# SCH_3_3v_regulator.net
KiCad netlist of a schematic drawn in Altium Designer
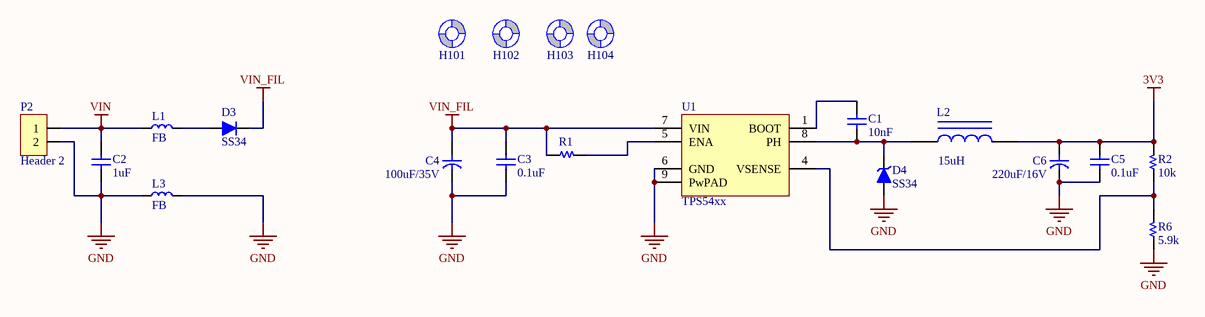
[diagram p0: SCH_3.3v_regulator.SchDoc]

(export (version "E")
  (design (tool "Eeschema 10.0.6"))
  (components
    (comp (ref "C1")
      (value "10nF")
      (footprint "C 0805")
      (description "Capacitor non-pol")
      (libsource (lib "chipfc_libs") (part "Capacitor NP"))
    )
    (comp (ref "C2")
      (value "1uF")
      (footprint "C 0805")
      (description "Capacitor non-pol")
      (libsource (lib "chipfc_libs") (part "Capacitor NP"))
    )
    (comp (ref "C3")
      (value "0.1uF")
      (footprint "C 0805")
      (description "Capacitor non-pol")
      (libsource (lib "chipfc_libs") (part "Capacitor NP"))
    )
    (comp (ref "C4")
      (value "100uF/35V")
      (footprint "C SMD ALU (D8)")
      (description "Capacitor pol")
      (libsource (lib "chipfc_libs") (part "Capacitor"))
    )
    (comp (ref "C5")
      (value "0.1uF")
      (footprint "C 0805")
      (description "Capacitor non-pol")
      (libsource (lib "chipfc_libs") (part "Capacitor NP"))
    )
    (comp (ref "C6")
      (value "220uF/16V")
      (footprint "C SMD ALU (D8)")
      (description "Capacitor pol")
      (libsource (lib "chipfc_libs") (part "Capacitor"))
    )
    (comp (ref "D3")
      (value "SS34")
      (footprint "Diode PowerDI123")
      (description "Default Diode")
      (libsource (lib "chipfc_libs") (part "Diode"))
    )
    (comp (ref "D4")
      (value "SS34")
      (footprint "DO-214AC (SMA)")
      (description "Zener Diode")
      (libsource (lib "chipfc_libs") (part "Diode Zener"))
    )
    (comp (ref "H101")
      (value "Screw Hole")
      (footprint "SCREW/3.2/7.0/M")
      (libsource (lib "chipfc_libs") (part "Screw Hole"))
    )
    (comp (ref "H102")
      (value "Screw Hole")
      (footprint "SCREW/3.2/7.0/M")
      (libsource (lib "chipfc_libs") (part "Screw Hole"))
    )
    (comp (ref "H103")
      (value "Screw Hole")
      (footprint "SCREW/3.2/7.0/M")
      (libsource (lib "chipfc_libs") (part "Screw Hole"))
    )
    (comp (ref "H104")
      (value "Screw Hole")
      (footprint "SCREW/3.2/7.0/M")
      (libsource (lib "chipfc_libs") (part "Screw Hole"))
    )
    (comp (ref "L1")
      (value "FB")
      (footprint "L 0805 (2012)")
      (description "Inductor")
      (libsource (lib "chipfc_libs") (part "Inductor"))
    )
    (comp (ref "L2")
      (value "15uH")
      (footprint "AXIAL-0.9")
      (description "Magnetic-Core Inductor")
      (fields (field (name "PUBLISHER") "Altium Limited"))
      (libsource (lib "Miscellaneous-Devices") (part "Inductor Iron"))
    )
    (comp (ref "L3")
      (value "FB")
      (footprint "L 0805 (2012)")
      (description "Inductor")
      (libsource (lib "chipfc_libs") (part "Inductor"))
    )
    (comp (ref "P2")
      (value "Header 2")
      (footprint "HDR/Header/2/BOX")
      (description "Header, 2-Pin")
      (libsource (lib "connectors") (part "Header 2"))
    )
    (comp (ref "R1")
      (value "R")
      (footprint "R 0805")
      (description "Resistor")
      (libsource (lib "chipfc_libs") (part "Resistor"))
    )
    (comp (ref "R2")
      (value "10k")
      (footprint "R 0805")
      (description "Resistor")
      (libsource (lib "chipfc_libs") (part "Resistor"))
    )
    (comp (ref "R6")
      (value "5.9k")
      (footprint "R 0805")
      (description "Resistor")
      (libsource (lib "chipfc_libs") (part "Resistor"))
    )
    (comp (ref "U1")
      (value "TPS54xx")
      (footprint "SOIC-8 EP")
      (description "3/5A, Wide input range, Step-down SWIFT DC-DC Converter")
      (libsource (lib "chipfc_libs") (part "TPS54xx"))
    )
  )
  (nets
    (net (code "1") (name "3V3") (class "Default")
      (node (ref "C5") (pin "1") (pinfunction "1_1") (pintype "passive"))
      (node (ref "C6") (pin "1") (pinfunction "1_1") (pintype "passive"))
      (node (ref "L2") (pin "2") (pinfunction "2_2") (pintype "passive"))
      (node (ref "R2") (pin "2") (pinfunction "2_2") (pintype "passive"))
    )
    (net (code "2") (name "GND") (class "Default")
      (node (ref "C2") (pin "2") (pinfunction "2_2") (pintype "passive"))
      (node (ref "C3") (pin "2") (pinfunction "2_2") (pintype "passive"))
      (node (ref "C4") (pin "2") (pinfunction "2_2") (pintype "passive"))
      (node (ref "C5") (pin "2") (pinfunction "2_2") (pintype "passive"))
      (node (ref "C6") (pin "2") (pinfunction "2_2") (pintype "passive"))
      (node (ref "D4") (pin "1") (pinfunction "A_1") (pintype "passive"))
      (node (ref "L3") (pin "1") (pinfunction "1_1") (pintype "passive"))
      (node (ref "L3") (pin "2") (pinfunction "2_2") (pintype "passive"))
      (node (ref "P2") (pin "2") (pinfunction "2_2") (pintype "passive"))
      (node (ref "R6") (pin "1") (pinfunction "1_1") (pintype "passive"))
      (node (ref "U1") (pin "6") (pinfunction "GND_6") (pintype "passive"))
      (node (ref "U1") (pin "9") (pinfunction "PwPAD_9") (pintype "passive"))
    )
    (net (code "3") (name "Net-(D3-A)") (class "Default")
      (node (ref "D3") (pin "1") (pinfunction "A_1") (pintype "passive"))
      (node (ref "L1") (pin "2") (pinfunction "2_2") (pintype "passive"))
    )
    (net (code "4") (name "Net-(D4-K)") (class "Default")
      (node (ref "C1") (pin "2") (pinfunction "2_2") (pintype "passive"))
      (node (ref "D4") (pin "2") (pinfunction "K_2") (pintype "passive"))
      (node (ref "L2") (pin "1") (pinfunction "1_1") (pintype "passive"))
      (node (ref "U1") (pin "8") (pinfunction "PH_8") (pintype "passive"))
    )
    (net (code "5") (name "Net-(U1-BOOT)") (class "Default")
      (node (ref "C1") (pin "1") (pinfunction "1_1") (pintype "passive"))
      (node (ref "U1") (pin "1") (pinfunction "BOOT_1") (pintype "passive"))
    )
    (net (code "6") (name "Net-(U1-ENA)") (class "Default")
      (node (ref "R1") (pin "2") (pinfunction "2_2") (pintype "passive"))
      (node (ref "U1") (pin "5") (pinfunction "ENA_5") (pintype "passive"))
    )
    (net (code "7") (name "Net-(U1-VSENSE)") (class "Default")
      (node (ref "R2") (pin "1") (pinfunction "1_1") (pintype "passive"))
      (node (ref "R6") (pin "2") (pinfunction "2_2") (pintype "passive"))
      (node (ref "U1") (pin "4") (pinfunction "VSENSE_4") (pintype "passive"))
    )
    (net (code "8") (name "VIN") (class "Default")
      (node (ref "C2") (pin "1") (pinfunction "1_1") (pintype "passive"))
      (node (ref "L1") (pin "1") (pinfunction "1_1") (pintype "passive"))
      (node (ref "P2") (pin "1") (pinfunction "1_1") (pintype "passive"))
    )
    (net (code "9") (name "VIN_FIL") (class "Default")
      (node (ref "C3") (pin "1") (pinfunction "1_1") (pintype "passive"))
      (node (ref "C4") (pin "1") (pinfunction "1_1") (pintype "passive"))
      (node (ref "D3") (pin "2") (pinfunction "K_2") (pintype "passive"))
      (node (ref "R1") (pin "1") (pinfunction "1_1") (pintype "passive"))
      (node (ref "U1") (pin "7") (pinfunction "VIN_7") (pintype "passive"))
    )
    (net (code "10") (name "unconnected-(H101-Screw-Pad1)") (class "Default")
      (node (ref "H101") (pin "1") (pinfunction "Screw_1") (pintype "passive"))
    )
    (net (code "11") (name "unconnected-(H102-Screw-Pad1)") (class "Default")
      (node (ref "H102") (pin "1") (pinfunction "Screw_1") (pintype "passive"))
    )
    (net (code "12") (name "unconnected-(H103-Screw-Pad1)") (class "Default")
      (node (ref "H103") (pin "1") (pinfunction "Screw_1") (pintype "passive"))
    )
    (net (code "13") (name "unconnected-(H104-Screw-Pad1)") (class "Default")
      (node (ref "H104") (pin "1") (pinfunction "Screw_1") (pintype "passive"))
    )
  )
)
